# Extras.net
KiCad netlist of a schematic drawn in Altium Designer
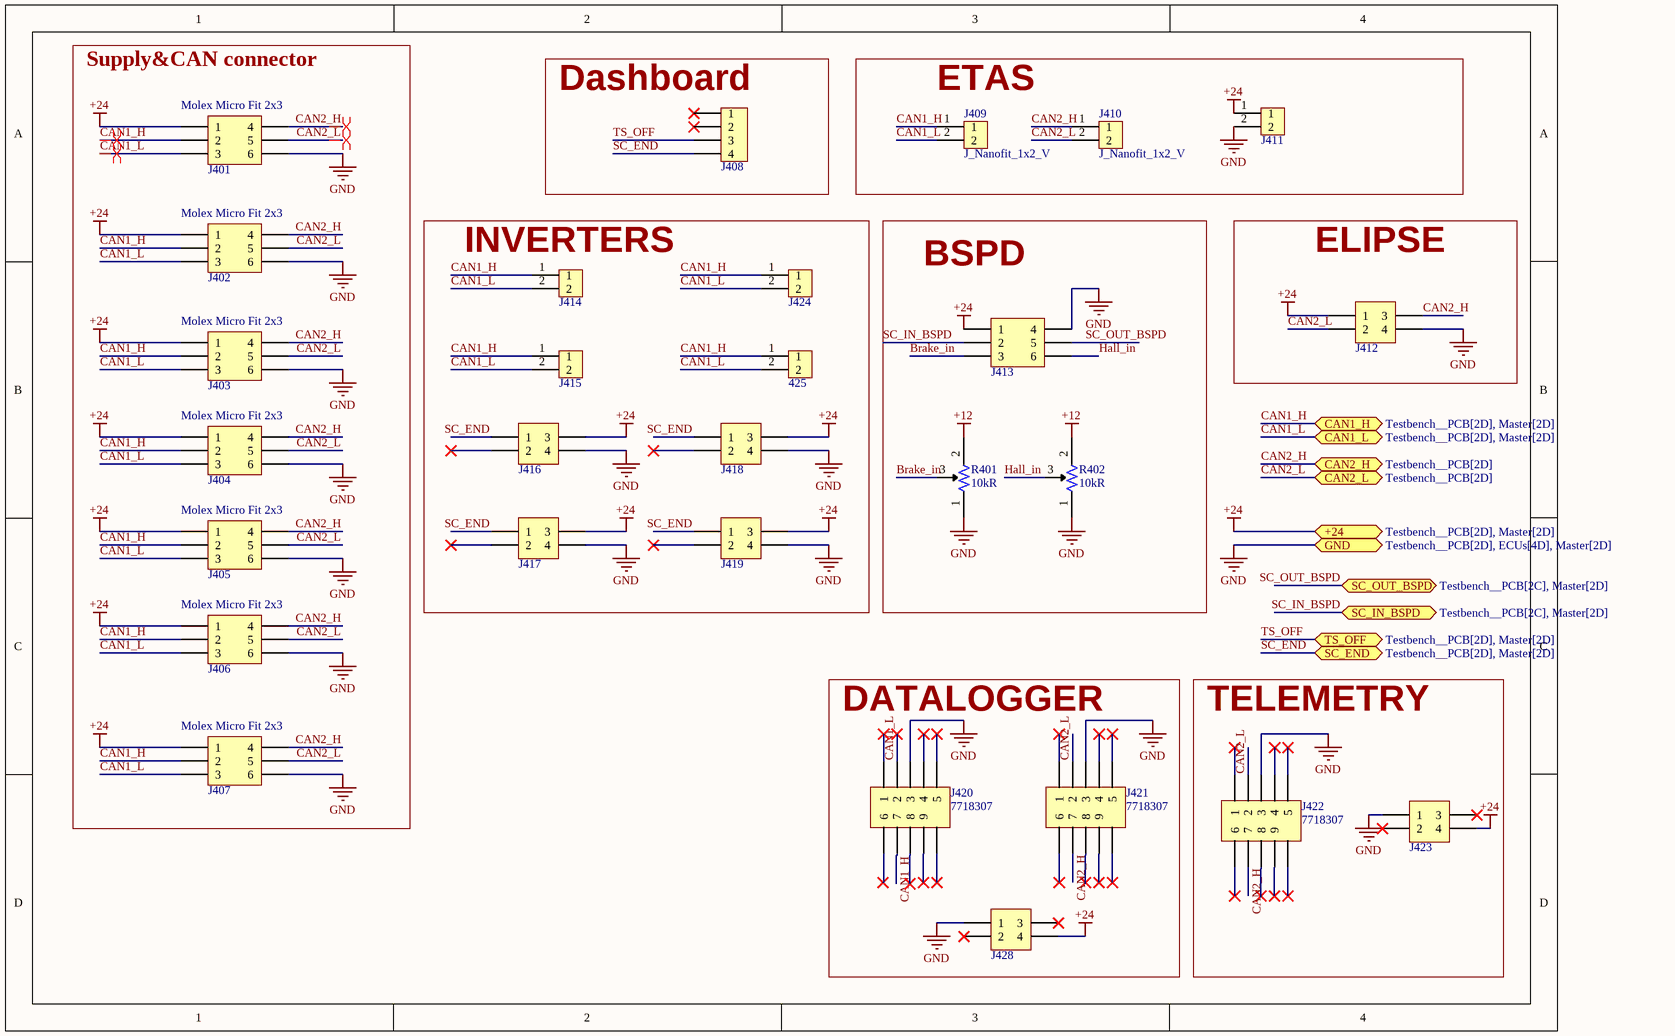
[diagram p0: Extras.SchDoc]

(export (version "E")
  (design (tool "Eeschema 10.0.6"))
  (components
    (comp (ref "425")
      (value "436500215")
      (footprint "J_MicroFit_2x1")
      (description "Header 1 Row Vertical Polarizing Peg 2 Pin SMT/Glow Wire Compatible Tin Plate")
      (libsource (lib "Electromechanical") (part "J_MicroFit_2x1"))
    )
    (comp (ref "J401")
      (value "Molex Micro Fit 2x3")
      (footprint "J_MicroFit_2x3_V")
      (description "Micro fit Header, 2 Row, Vertical, Polarizing Peg, 6 Pin, Tin Plate, SMT/Glow Wire, Kinked Leads")
      (fields
        (field (name "MANUFACTURER") "Molex")
        (field (name "MANUFACTURER PART NUMBER") "43045-0612")
        (field (name ".CREATOR") "DO")
      )
      (libsource (lib "Electromechanical") (part "J_MicroFit_2x3_V"))
    )
    (comp (ref "J402")
      (value "Molex Micro Fit 2x3")
      (footprint "J_MicroFit_2x3_V")
      (description "Micro fit Header, 2 Row, Vertical, Polarizing Peg, 6 Pin, Tin Plate, SMT/Glow Wire, Kinked Leads")
      (fields
        (field (name "MANUFACTURER") "Molex")
        (field (name "MANUFACTURER PART NUMBER") "43045-0612")
        (field (name ".CREATOR") "DO")
      )
      (libsource (lib "Electromechanical") (part "J_MicroFit_2x3_V"))
    )
    (comp (ref "J403")
      (value "Molex Micro Fit 2x3")
      (footprint "J_MicroFit_2x3_V")
      (description "Micro fit Header, 2 Row, Vertical, Polarizing Peg, 6 Pin, Tin Plate, SMT/Glow Wire, Kinked Leads")
      (fields
        (field (name "MANUFACTURER") "Molex")
        (field (name "MANUFACTURER PART NUMBER") "43045-0612")
        (field (name ".CREATOR") "DO")
      )
      (libsource (lib "Electromechanical") (part "J_MicroFit_2x3_V"))
    )
    (comp (ref "J404")
      (value "Molex Micro Fit 2x3")
      (footprint "J_MicroFit_2x3_V")
      (description "Micro fit Header, 2 Row, Vertical, Polarizing Peg, 6 Pin, Tin Plate, SMT/Glow Wire, Kinked Leads")
      (fields
        (field (name "MANUFACTURER") "Molex")
        (field (name "MANUFACTURER PART NUMBER") "43045-0612")
        (field (name ".CREATOR") "DO")
      )
      (libsource (lib "Electromechanical") (part "J_MicroFit_2x3_V"))
    )
    (comp (ref "J405")
      (value "Molex Micro Fit 2x3")
      (footprint "J_MicroFit_2x3_V")
      (description "Micro fit Header, 2 Row, Vertical, Polarizing Peg, 6 Pin, Tin Plate, SMT/Glow Wire, Kinked Leads")
      (fields
        (field (name "MANUFACTURER") "Molex")
        (field (name "MANUFACTURER PART NUMBER") "43045-0612")
        (field (name ".CREATOR") "DO")
      )
      (libsource (lib "Electromechanical") (part "J_MicroFit_2x3_V"))
    )
    (comp (ref "J406")
      (value "Molex Micro Fit 2x3")
      (footprint "J_MicroFit_2x3_V")
      (description "Micro fit Header, 2 Row, Vertical, Polarizing Peg, 6 Pin, Tin Plate, SMT/Glow Wire, Kinked Leads")
      (fields
        (field (name "MANUFACTURER") "Molex")
        (field (name "MANUFACTURER PART NUMBER") "43045-0612")
        (field (name ".CREATOR") "DO")
      )
      (libsource (lib "Electromechanical") (part "J_MicroFit_2x3_V"))
    )
    (comp (ref "J407")
      (value "Molex Micro Fit 2x3")
      (footprint "J_MicroFit_2x3_V")
      (description "Micro fit Header, 2 Row, Vertical, Polarizing Peg, 6 Pin, Tin Plate, SMT/Glow Wire, Kinked Leads")
      (fields
        (field (name "MANUFACTURER") "Molex")
        (field (name "MANUFACTURER PART NUMBER") "43045-0612")
        (field (name ".CREATOR") "DO")
      )
      (libsource (lib "Electromechanical") (part "J_MicroFit_2x3_V"))
    )
    (comp (ref "J408")
      (value "1053091204")
      (footprint "J_NanoFit_1x4_V")
      (description "Nano-Fit Vertical Header Through Hole 2.50mm Pitch Single Row 4 Circuits with Kinked Pins 0.38")
      (fields (field (name ".CREATOR") "DO"))
      (libsource (lib "Electromechanical") (part "J_NanoFit_1x4_V"))
    )
    (comp (ref "J409")
      (value "J_Nanofit_1x2_V")
      (footprint "J_NanoFit_1X2_V")
      (fields (field (name "MANUFACTURER") "Molex") (field (name "MANUFACTURER PART NUMBER") "1053092202"))
      (libsource (lib "Electromechanical") (part "J_Nanofit_1x2_V"))
    )
    (comp (ref "J410")
      (value "J_Nanofit_1x2_V")
      (footprint "J_NanoFit_1X2_V")
      (fields (field (name "MANUFACTURER") "Molex") (field (name "MANUFACTURER PART NUMBER") "1053092202"))
      (libsource (lib "Electromechanical") (part "J_Nanofit_1x2_V"))
    )
    (comp (ref "J411")
      (value "436500215")
      (footprint "J_MicroFit_2x1")
      (description "Header 1 Row Vertical Polarizing Peg 2 Pin SMT/Glow Wire Compatible Tin Plate")
      (libsource (lib "Electromechanical") (part "J_MicroFit_2x1"))
    )
    (comp (ref "J412")
      (value "J_NanoFit_2x2")
      (footprint "J_NanoFit_2x2_v")
      (description "Conn Nano-Fit Power HDR 4 POS 2.5mm Solder ST Through Hole 4 Terminal Single Port Tray")
      (libsource (lib "Electromechanical") (part "J_NanoFit_2x2"))
    )
    (comp (ref "J413")
      (value "43045-0612")
      (footprint "J_MicroFit_2x3_V")
      (description "Micro fit Header, 2 Row, Vertical, Polarizing Peg, 6 Pin, Tin Plate, SMT/Glow Wire, Kinked Leads")
      (fields (field (name "MANUFACTURER") "Molex") (field (name ".CREATOR") "DO"))
      (libsource (lib "Electromechanical") (part "J_MicroFit_2x3_V"))
    )
    (comp (ref "J414")
      (value "436500215")
      (footprint "J_MicroFit_2x1")
      (description "Header 1 Row Vertical Polarizing Peg 2 Pin SMT/Glow Wire Compatible Tin Plate")
      (libsource (lib "Electromechanical") (part "J_MicroFit_2x1"))
    )
    (comp (ref "J415")
      (value "436500215")
      (footprint "J_MicroFit_2x1")
      (description "Header 1 Row Vertical Polarizing Peg 2 Pin SMT/Glow Wire Compatible Tin Plate")
      (libsource (lib "Electromechanical") (part "J_MicroFit_2x1"))
    )
    (comp (ref "J416")
      (value "J_NanoFit_2x2")
      (footprint "J_NanoFit_2x2_v")
      (description "Conn Nano-Fit Power HDR 4 POS 2.5mm Solder ST Through Hole 4 Terminal Single Port Tray")
      (libsource (lib "Electromechanical") (part "J_NanoFit_2x2"))
    )
    (comp (ref "J417")
      (value "J_NanoFit_2x2")
      (footprint "J_NanoFit_2x2_v")
      (description "Conn Nano-Fit Power HDR 4 POS 2.5mm Solder ST Through Hole 4 Terminal Single Port Tray")
      (libsource (lib "Electromechanical") (part "J_NanoFit_2x2"))
    )
    (comp (ref "J418")
      (value "J_NanoFit_2x2")
      (footprint "J_NanoFit_2x2_v")
      (description "Conn Nano-Fit Power HDR 4 POS 2.5mm Solder ST Through Hole 4 Terminal Single Port Tray")
      (libsource (lib "Electromechanical") (part "J_NanoFit_2x2"))
    )
    (comp (ref "J419")
      (value "J_NanoFit_2x2")
      (footprint "J_NanoFit_2x2_v")
      (description "Conn Nano-Fit Power HDR 4 POS 2.5mm Solder ST Through Hole 4 Terminal Single Port Tray")
      (libsource (lib "Electromechanical") (part "J_NanoFit_2x2"))
    )
    (comp (ref "J420")
      (value "618009231221")
      (footprint "J_VGA_CONNECTOR")
      (description "9 Way Right Angle Through Hole PCB D-sub Connector Plug; 2.77mm; 2.84mm Pitch")
      (fields
        (field (name "MANUFACTURER") "Wurth Electronics")
        (field (name "SUPPLIER PART NUMBER 1") "7718307")
      )
      (libsource (lib "Electromechanical") (part "J_VGA_CONNECTOR"))
    )
    (comp (ref "J421")
      (value "618009231221")
      (footprint "J_VGA_CONNECTOR")
      (description "9 Way Right Angle Through Hole PCB D-sub Connector Plug; 2.77mm; 2.84mm Pitch")
      (fields
        (field (name "MANUFACTURER") "Wurth Electronics")
        (field (name "SUPPLIER PART NUMBER 1") "7718307")
      )
      (libsource (lib "Electromechanical") (part "J_VGA_CONNECTOR"))
    )
    (comp (ref "J422")
      (value "618009231221")
      (footprint "J_VGA_CONNECTOR")
      (description "9 Way Right Angle Through Hole PCB D-sub Connector Plug; 2.77mm; 2.84mm Pitch")
      (fields
        (field (name "MANUFACTURER") "Wurth Electronics")
        (field (name "SUPPLIER PART NUMBER 1") "7718307")
      )
      (libsource (lib "Electromechanical") (part "J_VGA_CONNECTOR"))
    )
    (comp (ref "J423")
      (value "J_NanoFit_2x2")
      (footprint "J_NanoFit_2x2_v")
      (description "Conn Nano-Fit Power HDR 4 POS 2.5mm Solder ST Through Hole 4 Terminal Single Port Tray")
      (libsource (lib "Electromechanical") (part "J_NanoFit_2x2"))
    )
    (comp (ref "J424")
      (value "436500215")
      (footprint "J_MicroFit_2x1")
      (description "Header 1 Row Vertical Polarizing Peg 2 Pin SMT/Glow Wire Compatible Tin Plate")
      (libsource (lib "Electromechanical") (part "J_MicroFit_2x1"))
    )
    (comp (ref "J428")
      (value "J_NanoFit_2x2")
      (footprint "J_NanoFit_2x2_v")
      (description "Conn Nano-Fit Power HDR 4 POS 2.5mm Solder ST Through Hole 4 Terminal Single Port Tray")
      (libsource (lib "Electromechanical") (part "J_NanoFit_2x2"))
    )
    (comp (ref "R401")
      (value "3296W-1-103LF")
      (footprint "R10k-VTR")
      (description "Trimmer, Cermet, Rest 10 Kilohms, PCB, 25 Turns, Pwr-Rtg 0.5W, 3296 Series")
      (fields
        (field (name "MANUFACTURER") "Bourns")
        (field (name "TOLERANCE") "10%")
        (field (name "RESISTANCE") "10kR")
        (field (name ".CREATOR") "DO")
      )
      (libsource (lib "Passives") (part "R10k-VTR"))
    )
    (comp (ref "R402")
      (value "3296W-1-103LF")
      (footprint "R10k-VTR")
      (description "Trimmer, Cermet, Rest 10 Kilohms, PCB, 25 Turns, Pwr-Rtg 0.5W, 3296 Series")
      (fields
        (field (name "MANUFACTURER") "Bourns")
        (field (name "TOLERANCE") "10%")
        (field (name "RESISTANCE") "10kR")
        (field (name ".CREATOR") "DO")
      )
      (libsource (lib "Passives") (part "R10k-VTR"))
    )
  )
  (nets
    (net (code "1") (name "+12") (class "Default")
      (node (ref "R401") (pin "2") (pinfunction "2_2") (pintype "passive"))
      (node (ref "R402") (pin "2") (pinfunction "2_2") (pintype "passive"))
    )
    (net (code "2") (name "+24") (class "Default")
      (node (ref "J401") (pin "1") (pinfunction "1_1") (pintype "passive"))
      (node (ref "J402") (pin "1") (pinfunction "1_1") (pintype "passive"))
      (node (ref "J403") (pin "1") (pinfunction "1_1") (pintype "passive"))
      (node (ref "J404") (pin "1") (pinfunction "1_1") (pintype "passive"))
      (node (ref "J405") (pin "1") (pinfunction "1_1") (pintype "passive"))
      (node (ref "J406") (pin "1") (pinfunction "1_1") (pintype "passive"))
      (node (ref "J407") (pin "1") (pinfunction "1_1") (pintype "passive"))
      (node (ref "J411") (pin "1") (pinfunction "1_1") (pintype "passive"))
      (node (ref "J412") (pin "1") (pinfunction "1_1") (pintype "passive"))
      (node (ref "J413") (pin "1") (pinfunction "1_1") (pintype "passive"))
      (node (ref "J416") (pin "3") (pinfunction "3_3") (pintype "passive"))
      (node (ref "J417") (pin "3") (pinfunction "3_3") (pintype "passive"))
      (node (ref "J418") (pin "3") (pinfunction "3_3") (pintype "passive"))
      (node (ref "J419") (pin "3") (pinfunction "3_3") (pintype "passive"))
      (node (ref "J423") (pin "4") (pinfunction "4_4") (pintype "passive"))
      (node (ref "J428") (pin "4") (pinfunction "4_4") (pintype "passive"))
    )
    (net (code "3") (name "/Brake_in") (class "Default")
      (node (ref "J413") (pin "3") (pinfunction "3_3") (pintype "passive"))
      (node (ref "R401") (pin "3") (pinfunction "3_3") (pintype "passive"))
    )
    (net (code "4") (name "/CAN1_H") (class "Default")
      (node (ref "425") (pin "1") (pinfunction "1_1") (pintype "passive"))
      (node (ref "J401") (pin "2") (pinfunction "2_2") (pintype "passive"))
      (node (ref "J402") (pin "2") (pinfunction "2_2") (pintype "passive"))
      (node (ref "J403") (pin "2") (pinfunction "2_2") (pintype "passive"))
      (node (ref "J404") (pin "2") (pinfunction "2_2") (pintype "passive"))
      (node (ref "J405") (pin "2") (pinfunction "2_2") (pintype "passive"))
      (node (ref "J406") (pin "2") (pinfunction "2_2") (pintype "passive"))
      (node (ref "J407") (pin "2") (pinfunction "2_2") (pintype "passive"))
      (node (ref "J409") (pin "1") (pinfunction "1_1") (pintype "passive"))
      (node (ref "J414") (pin "1") (pinfunction "1_1") (pintype "passive"))
      (node (ref "J415") (pin "1") (pinfunction "1_1") (pintype "passive"))
      (node (ref "J420") (pin "7") (pinfunction "7_7") (pintype "passive"))
      (node (ref "J424") (pin "1") (pinfunction "1_1") (pintype "passive"))
    )
    (net (code "5") (name "/CAN1_L") (class "Default")
      (node (ref "425") (pin "2") (pinfunction "2_2") (pintype "passive"))
      (node (ref "J401") (pin "3") (pinfunction "3_3") (pintype "passive"))
      (node (ref "J402") (pin "3") (pinfunction "3_3") (pintype "passive"))
      (node (ref "J403") (pin "3") (pinfunction "3_3") (pintype "passive"))
      (node (ref "J404") (pin "3") (pinfunction "3_3") (pintype "passive"))
      (node (ref "J405") (pin "3") (pinfunction "3_3") (pintype "passive"))
      (node (ref "J406") (pin "3") (pinfunction "3_3") (pintype "passive"))
      (node (ref "J407") (pin "3") (pinfunction "3_3") (pintype "passive"))
      (node (ref "J409") (pin "2") (pinfunction "2_2") (pintype "passive"))
      (node (ref "J414") (pin "2") (pinfunction "2_2") (pintype "passive"))
      (node (ref "J415") (pin "2") (pinfunction "2_2") (pintype "passive"))
      (node (ref "J420") (pin "2") (pinfunction "2_2") (pintype "passive"))
      (node (ref "J424") (pin "2") (pinfunction "2_2") (pintype "passive"))
    )
    (net (code "6") (name "/CAN2_H") (class "Default")
      (node (ref "J401") (pin "4") (pinfunction "4_4") (pintype "passive"))
      (node (ref "J402") (pin "4") (pinfunction "4_4") (pintype "passive"))
      (node (ref "J403") (pin "4") (pinfunction "4_4") (pintype "passive"))
      (node (ref "J404") (pin "4") (pinfunction "4_4") (pintype "passive"))
      (node (ref "J405") (pin "4") (pinfunction "4_4") (pintype "passive"))
      (node (ref "J406") (pin "4") (pinfunction "4_4") (pintype "passive"))
      (node (ref "J407") (pin "4") (pinfunction "4_4") (pintype "passive"))
      (node (ref "J410") (pin "1") (pinfunction "1_1") (pintype "passive"))
      (node (ref "J412") (pin "3") (pinfunction "3_3") (pintype "passive"))
      (node (ref "J421") (pin "7") (pinfunction "7_7") (pintype "passive"))
      (node (ref "J422") (pin "7") (pinfunction "7_7") (pintype "passive"))
    )
    (net (code "7") (name "/CAN2_L") (class "Default")
      (node (ref "J401") (pin "5") (pinfunction "5_5") (pintype "passive"))
      (node (ref "J402") (pin "5") (pinfunction "5_5") (pintype "passive"))
      (node (ref "J403") (pin "5") (pinfunction "5_5") (pintype "passive"))
      (node (ref "J404") (pin "5") (pinfunction "5_5") (pintype "passive"))
      (node (ref "J405") (pin "5") (pinfunction "5_5") (pintype "passive"))
      (node (ref "J406") (pin "5") (pinfunction "5_5") (pintype "passive"))
      (node (ref "J407") (pin "5") (pinfunction "5_5") (pintype "passive"))
      (node (ref "J410") (pin "2") (pinfunction "2_2") (pintype "passive"))
      (node (ref "J412") (pin "2") (pinfunction "2_2") (pintype "passive"))
      (node (ref "J421") (pin "2") (pinfunction "2_2") (pintype "passive"))
      (node (ref "J422") (pin "2") (pinfunction "2_2") (pintype "passive"))
    )
    (net (code "8") (name "/Hall_in") (class "Default")
      (node (ref "J413") (pin "6") (pinfunction "6_6") (pintype "passive"))
      (node (ref "R402") (pin "3") (pinfunction "3_3") (pintype "passive"))
    )
    (net (code "9") (name "/SC_END") (class "Default")
      (node (ref "J408") (pin "4") (pinfunction "4_4") (pintype "passive"))
      (node (ref "J416") (pin "1") (pinfunction "1_1") (pintype "passive"))
      (node (ref "J417") (pin "1") (pinfunction "1_1") (pintype "passive"))
      (node (ref "J418") (pin "1") (pinfunction "1_1") (pintype "passive"))
      (node (ref "J419") (pin "1") (pinfunction "1_1") (pintype "passive"))
    )
    (net (code "10") (name "/SC_IN_BSPD") (class "Default")
      (node (ref "J413") (pin "2") (pinfunction "2_2") (pintype "passive"))
    )
    (net (code "11") (name "/SC_OUT_BSPD") (class "Default")
      (node (ref "J413") (pin "5") (pinfunction "5_5") (pintype "passive"))
    )
    (net (code "12") (name "/TS_OFF") (class "Default")
      (node (ref "J408") (pin "3") (pinfunction "3_3") (pintype "passive"))
    )
    (net (code "13") (name "GND") (class "Default")
      (node (ref "J401") (pin "6") (pinfunction "6_6") (pintype "passive"))
      (node (ref "J402") (pin "6") (pinfunction "6_6") (pintype "passive"))
      (node (ref "J403") (pin "6") (pinfunction "6_6") (pintype "passive"))
      (node (ref "J404") (pin "6") (pinfunction "6_6") (pintype "passive"))
      (node (ref "J405") (pin "6") (pinfunction "6_6") (pintype "passive"))
      (node (ref "J406") (pin "6") (pinfunction "6_6") (pintype "passive"))
      (node (ref "J407") (pin "6") (pinfunction "6_6") (pintype "passive"))
      (node (ref "J411") (pin "2") (pinfunction "2_2") (pintype "passive"))
      (node (ref "J412") (pin "4") (pinfunction "4_4") (pintype "passive"))
      (node (ref "J413") (pin "4") (pinfunction "4_4") (pintype "passive"))
      (node (ref "J416") (pin "4") (pinfunction "4_4") (pintype "passive"))
      (node (ref "J417") (pin "4") (pinfunction "4_4") (pintype "passive"))
      (node (ref "J418") (pin "4") (pinfunction "4_4") (pintype "passive"))
      (node (ref "J419") (pin "4") (pinfunction "4_4") (pintype "passive"))
      (node (ref "J420") (pin "3") (pinfunction "3_3") (pintype "passive"))
      (node (ref "J421") (pin "3") (pinfunction "3_3") (pintype "passive"))
      (node (ref "J422") (pin "3") (pinfunction "3_3") (pintype "passive"))
      (node (ref "J423") (pin "1") (pinfunction "1_1") (pintype "passive"))
      (node (ref "J428") (pin "1") (pinfunction "1_1") (pintype "passive"))
      (node (ref "R401") (pin "1") (pinfunction "2_1") (pintype "passive"))
      (node (ref "R402") (pin "1") (pinfunction "2_1") (pintype "passive"))
    )
    (net (code "14") (name "unconnected-(J408-Pad1)") (class "Default")
      (node (ref "J408") (pin "1") (pinfunction "1_1") (pintype "passive+no_connect"))
    )
    (net (code "15") (name "unconnected-(J408-Pad2)") (class "Default")
      (node (ref "J408") (pin "2") (pinfunction "2_2") (pintype "passive+no_connect"))
    )
    (net (code "16") (name "unconnected-(J416-Pad2)") (class "Default")
      (node (ref "J416") (pin "2") (pinfunction "2_2") (pintype "passive+no_connect"))
    )
    (net (code "17") (name "unconnected-(J417-Pad2)") (class "Default")
      (node (ref "J417") (pin "2") (pinfunction "2_2") (pintype "passive+no_connect"))
    )
    (net (code "18") (name "unconnected-(J418-Pad2)") (class "Default")
      (node (ref "J418") (pin "2") (pinfunction "2_2") (pintype "passive+no_connect"))
    )
    (net (code "19") (name "unconnected-(J419-Pad2)") (class "Default")
      (node (ref "J419") (pin "2") (pinfunction "2_2") (pintype "passive+no_connect"))
    )
    (net (code "20") (name "unconnected-(J420-Pad1)") (class "Default")
      (node (ref "J420") (pin "1") (pinfunction "1_1") (pintype "passive+no_connect"))
    )
    (net (code "21") (name "unconnected-(J420-Pad4)") (class "Default")
      (node (ref "J420") (pin "4") (pinfunction "4_4") (pintype "passive+no_connect"))
    )
    (net (code "22") (name "unconnected-(J420-Pad5)") (class "Default")
      (node (ref "J420") (pin "5") (pinfunction "5_5") (pintype "passive+no_connect"))
    )
    (net (code "23") (name "unconnected-(J420-Pad6)") (class "Default")
      (node (ref "J420") (pin "6") (pinfunction "6_6") (pintype "passive+no_connect"))
    )
    (net (code "24") (name "unconnected-(J420-Pad8)") (class "Default")
      (node (ref "J420") (pin "8") (pinfunction "8_8") (pintype "passive+no_connect"))
    )
    (net (code "25") (name "unconnected-(J420-Pad9)") (class "Default")
      (node (ref "J420") (pin "9") (pinfunction "9_9") (pintype "passive+no_connect"))
    )
    (net (code "26") (name "unconnected-(J420-PadSHIELD)") (class "Default")
      (node (ref "J420") (pin "SHIELD") (pinfunction "SHIELD_SHIELD") (pintype "passive+no_connect"))
    )
    (net (code "27") (name "unconnected-(J421-Pad1)") (class "Default")
      (node (ref "J421") (pin "1") (pinfunction "1_1") (pintype "passive+no_connect"))
    )
    (net (code "28") (name "unconnected-(J421-Pad4)") (class "Default")
      (node (ref "J421") (pin "4") (pinfunction "4_4") (pintype "passive+no_connect"))
    )
    (net (code "29") (name "unconnected-(J421-Pad5)") (class "Default")
      (node (ref "J421") (pin "5") (pinfunction "5_5") (pintype "passive+no_connect"))
    )
    (net (code "30") (name "unconnected-(J421-Pad6)") (class "Default")
      (node (ref "J421") (pin "6") (pinfunction "6_6") (pintype "passive+no_connect"))
    )
    (net (code "31") (name "unconnected-(J421-Pad8)") (class "Default")
      (node (ref "J421") (pin "8") (pinfunction "8_8") (pintype "passive"))
    )
    (net (code "32") (name "unconnected-(J421-Pad9)") (class "Default")
      (node (ref "J421") (pin "9") (pinfunction "9_9") (pintype "passive+no_connect"))
    )
    (net (code "33") (name "unconnected-(J421-PadSHIELD)") (class "Default")
      (node (ref "J421") (pin "SHIELD") (pinfunction "SHIELD_SHIELD") (pintype "passive+no_connect"))
    )
    (net (code "34") (name "unconnected-(J422-Pad1)") (class "Default")
      (node (ref "J422") (pin "1") (pinfunction "1_1") (pintype "passive+no_connect"))
    )
    (net (code "35") (name "unconnected-(J422-Pad4)") (class "Default")
      (node (ref "J422") (pin "4") (pinfunction "4_4") (pintype "passive+no_connect"))
    )
    (net (code "36") (name "unconnected-(J422-Pad5)") (class "Default")
      (node (ref "J422") (pin "5") (pinfunction "5_5") (pintype "passive+no_connect"))
    )
    (net (code "37") (name "unconnected-(J422-Pad6)") (class "Default")
      (node (ref "J422") (pin "6") (pinfunction "6_6") (pintype "passive+no_connect"))
    )
    (net (code "38") (name "unconnected-(J422-Pad8)") (class "Default")
      (node (ref "J422") (pin "8") (pinfunction "8_8") (pintype "passive"))
    )
    (net (code "39") (name "unconnected-(J422-Pad9)") (class "Default")
      (node (ref "J422") (pin "9") (pinfunction "9_9") (pintype "passive+no_connect"))
    )
    (net (code "40") (name "unconnected-(J422-PadSHIELD)") (class "Default")
      (node (ref "J422") (pin "SHIELD") (pinfunction "SHIELD_SHIELD") (pintype "passive+no_connect"))
    )
    (net (code "41") (name "unconnected-(J423-Pad2)") (class "Default")
      (node (ref "J423") (pin "2") (pinfunction "2_2") (pintype "passive+no_connect"))
    )
    (net (code "42") (name "unconnected-(J423-Pad3)") (class "Default")
      (node (ref "J423") (pin "3") (pinfunction "3_3") (pintype "passive+no_connect"))
    )
    (net (code "43") (name "unconnected-(J428-Pad2)") (class "Default")
      (node (ref "J428") (pin "2") (pinfunction "2_2") (pintype "passive+no_connect"))
    )
    (net (code "44") (name "unconnected-(J428-Pad3)") (class "Default")
      (node (ref "J428") (pin "3") (pinfunction "3_3") (pintype "passive+no_connect"))
    )
  )
)
